# UIAPduino_Pro_Micro_CH32V006_V1dot1.net
KiCad netlist of a schematic drawn in EAGLE
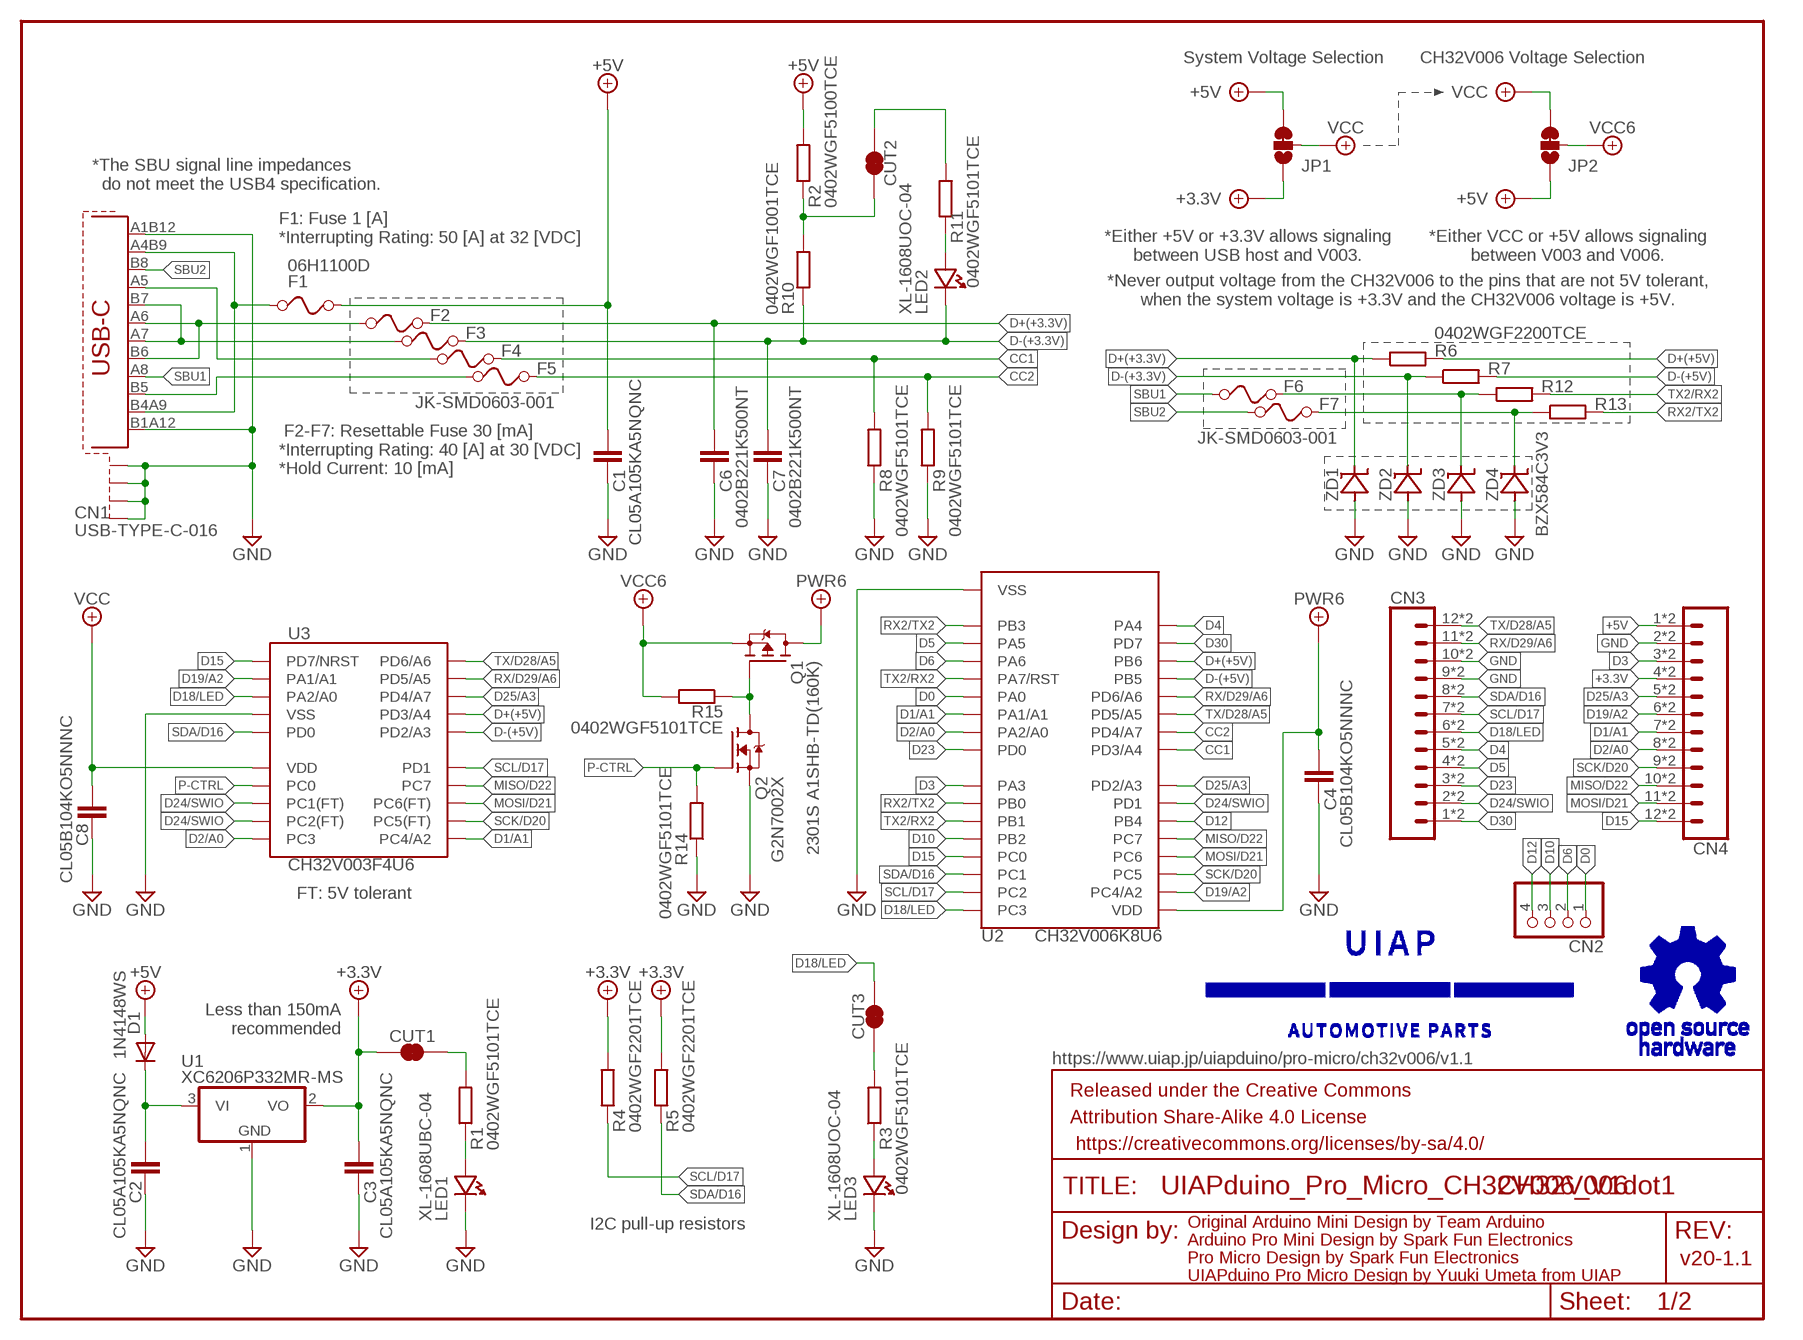
[diagram p0: schematic, sheet 1]
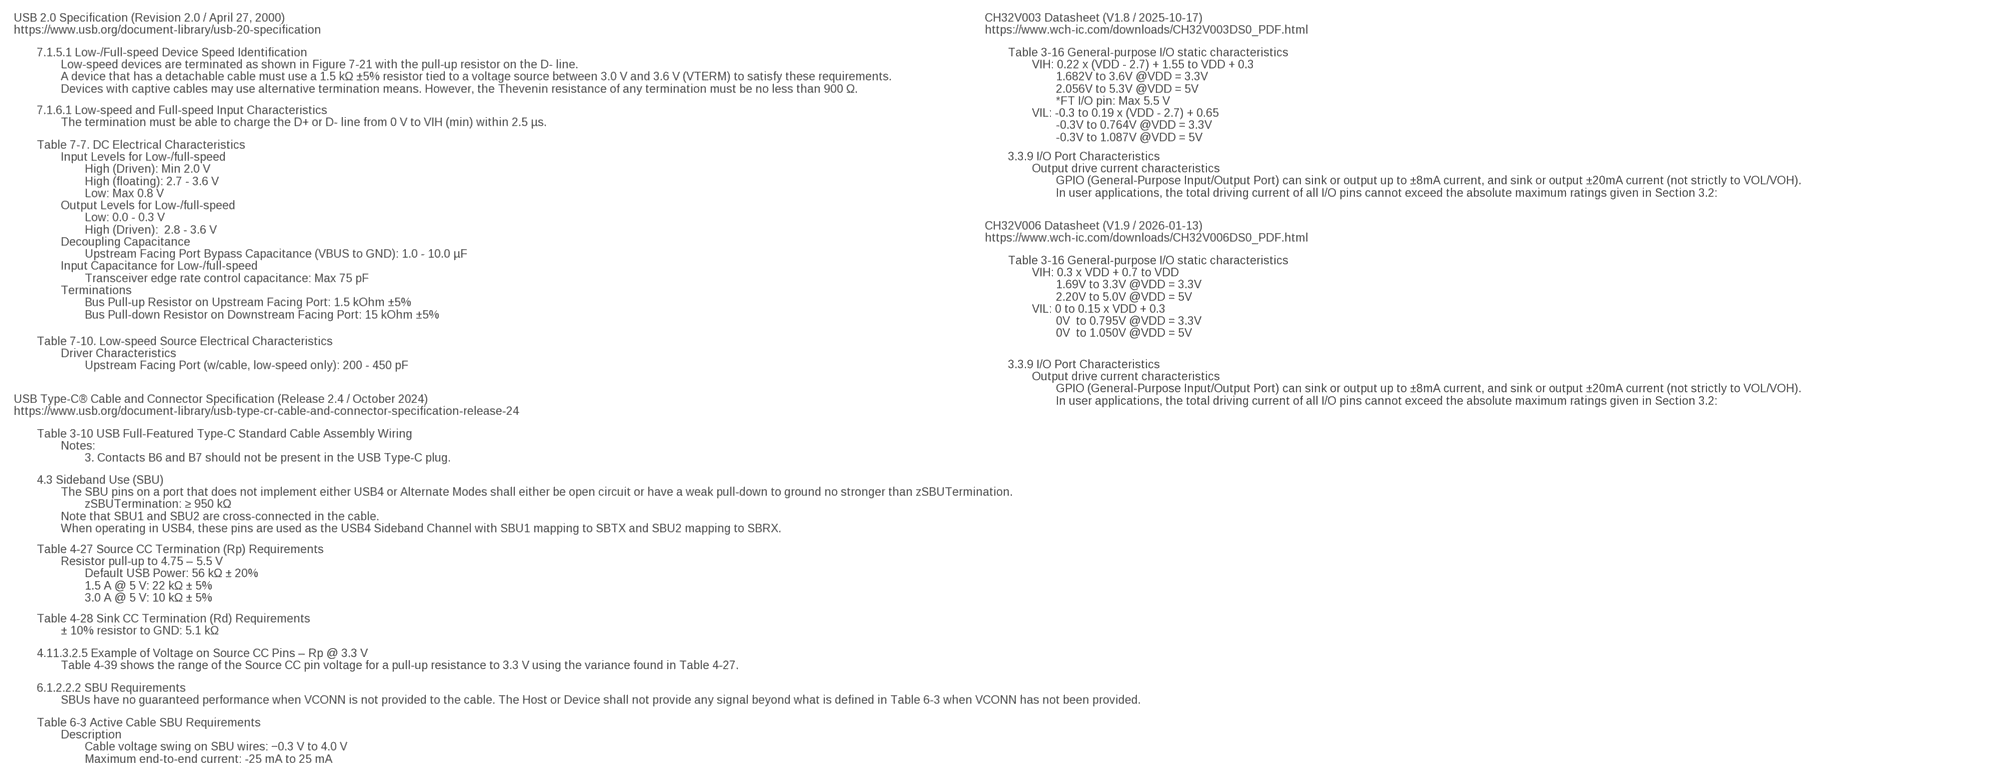
[diagram p1: schematic, sheet 2]

(export (version "E")
  (design (tool "Eeschema 10.0.6"))
  (components
    (comp (ref "C1")
      (value "CL05A105KA5NQNC")
      (footprint "eagle-import:1005")
      (libsource (lib "eagle-import") (part "C1005"))
    )
    (comp (ref "C2")
      (value "CL05A105KA5NQNC")
      (footprint "eagle-import:1005")
      (libsource (lib "eagle-import") (part "C1005"))
    )
    (comp (ref "C3")
      (value "CL05A105KA5NQNC")
      (footprint "eagle-import:1005")
      (libsource (lib "eagle-import") (part "C1005"))
    )
    (comp (ref "C4")
      (value "CL05B104KO5NNNC")
      (footprint "eagle-import:1005")
      (libsource (lib "eagle-import") (part "C1005"))
    )
    (comp (ref "C6")
      (value "0402B221K500NT")
      (footprint "eagle-import:1005")
      (libsource (lib "eagle-import") (part "C1005"))
    )
    (comp (ref "C7")
      (value "0402B221K500NT")
      (footprint "eagle-import:1005")
      (libsource (lib "eagle-import") (part "C1005"))
    )
    (comp (ref "C8")
      (value "CL05B104KO5NNNC")
      (footprint "eagle-import:1005")
      (libsource (lib "eagle-import") (part "C1005"))
    )
    (comp (ref "CN1")
      (value "USB-TYPE-C-016")
      (footprint "eagle-import:USB-TYPE-C-016")
      (libsource (lib "eagle-import") (part "USB-TYPE-C-016"))
    )
    (comp (ref "CN2")
      (value "PH-2X2")
      (footprint "eagle-import:2X02")
      (libsource (lib "eagle-import") (part "PH-2X2"))
    )
    (comp (ref "CN3")
      (value "CONN_12CASTLE_0.9MM")
      (footprint "eagle-import:1X12_CASTELLATED_0.9MM")
      (libsource (lib "eagle-import") (part "CONN_12CASTLE_0.9MM"))
    )
    (comp (ref "CN4")
      (value "CONN_12CASTLE_0.9MM")
      (footprint "eagle-import:1X12_CASTELLATED_0.9MM")
      (libsource (lib "eagle-import") (part "CONN_12CASTLE_0.9MM"))
    )
    (comp (ref "CUT1")
      (value "SMT-JP-2-NC")
      (footprint "eagle-import:SMT-JUMPER_2_NC_SILK_ROUND")
      (libsource (lib "eagle-import") (part "SMT-JP-2-NC"))
    )
    (comp (ref "CUT2")
      (value "SMT-JP-2-NC")
      (footprint "eagle-import:SMT-JUMPER_2_NC_SILK_ROUND")
      (libsource (lib "eagle-import") (part "SMT-JP-2-NC"))
    )
    (comp (ref "CUT3")
      (value "SMT-JP-2-NC")
      (footprint "eagle-import:SMT-JUMPER_2_NC_SILK_ROUND")
      (libsource (lib "eagle-import") (part "SMT-JP-2-NC"))
    )
    (comp (ref "D1")
      (value "1N4148WS")
      (footprint "eagle-import:SOD-523")
      (libsource (lib "eagle-import") (part "1N4148WT"))
    )
    (comp (ref "F1")
      (value "06H1100D")
      (footprint "eagle-import:1608")
      (libsource (lib "eagle-import") (part "06H1100D"))
    )
    (comp (ref "F2")
      (value "JK-SMD0603-001")
      (footprint "eagle-import:1608")
      (fields
        (field (name "JLCPCB-PART-#") "C2687114")
        (field (name "URL") "https://jlcpcb.com/partdetail/2790518-Jinrui_JK_SMD0603001/C2687114")
      )
      (libsource (lib "eagle-import") (part "06H1100D"))
    )
    (comp (ref "F3")
      (value "JK-SMD0603-001")
      (footprint "eagle-import:1608")
      (fields
        (field (name "JLCPCB-PART-#") "C2687114")
        (field (name "URL") "https://jlcpcb.com/partdetail/2790518-Jinrui_JK_SMD0603001/C2687114")
      )
      (libsource (lib "eagle-import") (part "06H1100D"))
    )
    (comp (ref "F4")
      (value "JK-SMD0603-001")
      (footprint "eagle-import:1608")
      (fields
        (field (name "JLCPCB-PART-#") "C2687114")
        (field (name "URL") "https://jlcpcb.com/partdetail/2790518-Jinrui_JK_SMD0603001/C2687114")
      )
      (libsource (lib "eagle-import") (part "06H1100D"))
    )
    (comp (ref "F5")
      (value "JK-SMD0603-001")
      (footprint "eagle-import:1608")
      (fields
        (field (name "JLCPCB-PART-#") "C2687114")
        (field (name "URL") "https://jlcpcb.com/partdetail/2790518-Jinrui_JK_SMD0603001/C2687114")
      )
      (libsource (lib "eagle-import") (part "06H1100D"))
    )
    (comp (ref "F6")
      (value "JK-SMD0603-001")
      (footprint "eagle-import:1608")
      (fields
        (field (name "JLCPCB-PART-#") "C2687114")
        (field (name "URL") "https://jlcpcb.com/partdetail/2790518-Jinrui_JK_SMD0603001/C2687114")
      )
      (libsource (lib "eagle-import") (part "06H1100D"))
    )
    (comp (ref "F7")
      (value "JK-SMD0603-001")
      (footprint "eagle-import:1608")
      (fields
        (field (name "JLCPCB-PART-#") "C2687114")
        (field (name "URL") "https://jlcpcb.com/partdetail/2790518-Jinrui_JK_SMD0603001/C2687114")
      )
      (libsource (lib "eagle-import") (part "06H1100D"))
    )
    (comp (ref "FRAME1")
      (value "FRAME-LETTER")
      (footprint "eagle-import:CREATIVE_COMMONS")
      (libsource (lib "eagle-import") (part "FRAME-LETTER"))
    )
    (comp (ref "JP1")
      (value "SMT-JP-3-NO-NC")
      (footprint "eagle-import:SMT-JUMPER_3_1-NC_TRACE_SILK")
      (libsource (lib "eagle-import") (part "SMT-JP-3-NO-NC"))
    )
    (comp (ref "JP2")
      (value "SMT-JP-3-NO-NC")
      (footprint "eagle-import:SMT-JUMPER_3_1-NC_TRACE_SILK")
      (libsource (lib "eagle-import") (part "SMT-JP-3-NO-NC"))
    )
    (comp (ref "LED1")
      (value "XL-1608UBC-04")
      (footprint "eagle-import:1608-LED")
      (libsource (lib "eagle-import") (part "XL-1608UBC-04"))
    )
    (comp (ref "LED2")
      (value "XL-1608UOC-04")
      (footprint "eagle-import:1608-LED")
      (libsource (lib "eagle-import") (part "XL-1608UOC-04"))
    )
    (comp (ref "LED3")
      (value "XL-1608UOC-04")
      (footprint "eagle-import:1608-LED")
      (libsource (lib "eagle-import") (part "XL-1608UOC-04"))
    )
    (comp (ref "Q1")
      (value "2301S A1SHB-TD(160K)")
      (footprint "eagle-import:SOT-23F_TOS-L")
      (libsource (lib "eagle-import") (part "2301S_A1SHB-TD(160K)"))
    )
    (comp (ref "Q2")
      (value "G2N7002X")
      (footprint "eagle-import:SOT-523")
      (libsource (lib "eagle-import") (part "G2N7002X"))
    )
    (comp (ref "R1")
      (value "0402WGF5101TCE")
      (footprint "eagle-import:1005")
      (libsource (lib "eagle-import") (part "R1005"))
    )
    (comp (ref "R2")
      (value "0402WGF5100TCE")
      (footprint "eagle-import:1005")
      (libsource (lib "eagle-import") (part "R1005"))
    )
    (comp (ref "R3")
      (value "0402WGF5101TCE")
      (footprint "eagle-import:1005")
      (libsource (lib "eagle-import") (part "R1005"))
    )
    (comp (ref "R4")
      (value "0402WGF2201TCE")
      (footprint "eagle-import:1005")
      (libsource (lib "eagle-import") (part "R1005"))
    )
    (comp (ref "R5")
      (value "0402WGF2201TCE")
      (footprint "eagle-import:1005")
      (libsource (lib "eagle-import") (part "R1005"))
    )
    (comp (ref "R6")
      (value "0402WGF2200TCE")
      (footprint "eagle-import:1005")
      (libsource (lib "eagle-import") (part "R1005"))
    )
    (comp (ref "R7")
      (value "0402WGF2200TCE")
      (footprint "eagle-import:1005")
      (libsource (lib "eagle-import") (part "R1005"))
    )
    (comp (ref "R8")
      (value "0402WGF5101TCE")
      (footprint "eagle-import:1005")
      (libsource (lib "eagle-import") (part "R1005"))
    )
    (comp (ref "R9")
      (value "0402WGF5101TCE")
      (footprint "eagle-import:1005")
      (libsource (lib "eagle-import") (part "R1005"))
    )
    (comp (ref "R10")
      (value "0402WGF1001TCE")
      (footprint "eagle-import:1005")
      (libsource (lib "eagle-import") (part "R1005"))
    )
    (comp (ref "R11")
      (value "0402WGF5101TCE")
      (footprint "eagle-import:1005")
      (libsource (lib "eagle-import") (part "R1005"))
    )
    (comp (ref "R12")
      (value "0402WGF2200TCE")
      (footprint "eagle-import:1005")
      (libsource (lib "eagle-import") (part "R1005"))
    )
    (comp (ref "R13")
      (value "0402WGF2200TCE")
      (footprint "eagle-import:1005")
      (libsource (lib "eagle-import") (part "R1005"))
    )
    (comp (ref "R14")
      (value "0402WGF5101TCE")
      (footprint "eagle-import:1005")
      (libsource (lib "eagle-import") (part "R1005"))
    )
    (comp (ref "R15")
      (value "0402WGF5101TCE")
      (footprint "eagle-import:1005")
      (libsource (lib "eagle-import") (part "R1005"))
    )
    (comp (ref "U1")
      (value "XC6206P332MR-MS")
      (footprint "eagle-import:SOT-23F_TOS-L")
      (libsource (lib "eagle-import") (part "XC6206P332MR-MS"))
    )
    (comp (ref "U2")
      (value "CH32V006K8U6")
      (footprint "eagle-import:QFN32-400X400X100")
      (libsource (lib "eagle-import") (part "CH32V006K8U6"))
    )
    (comp (ref "U3")
      (value "CH32V003F4U6")
      (footprint "eagle-import:QFN20-300X300X100-L")
      (libsource (lib "eagle-import") (part "CH32V003F4U6-L"))
    )
    (comp (ref "ZD1")
      (value "BZX584C3V3")
      (footprint "eagle-import:SOD-523")
      (libsource (lib "eagle-import") (part "BZX584C3V3"))
    )
    (comp (ref "ZD2")
      (value "BZX584C3V3")
      (footprint "eagle-import:SOD-523")
      (libsource (lib "eagle-import") (part "BZX584C3V3"))
    )
    (comp (ref "ZD3")
      (value "BZX584C3V3")
      (footprint "eagle-import:SOD-523")
      (libsource (lib "eagle-import") (part "BZX584C3V3"))
    )
    (comp (ref "ZD4")
      (value "BZX584C3V3")
      (footprint "eagle-import:SOD-523")
      (libsource (lib "eagle-import") (part "BZX584C3V3"))
    )
  )
  (nets
    (net (code "1") (name "+3.3V") (class "Default")
      (node (ref "C3") (pin "1") (pinfunction "1_1") (pintype "passive"))
      (node (ref "CN4") (pin "4") (pinfunction "4_4") (pintype "passive"))
      (node (ref "CN4") (pin "4B") (pinfunction "4_4B") (pintype "passive"))
      (node (ref "CUT1") (pin "2") (pinfunction "2_2") (pintype "passive"))
      (node (ref "JP1") (pin "1") (pinfunction "1_1") (pintype "passive"))
      (node (ref "R4") (pin "2") (pinfunction "2_2") (pintype "passive"))
      (node (ref "R5") (pin "2") (pinfunction "2_2") (pintype "passive"))
      (node (ref "U1") (pin "2") (pinfunction "VO_2") (pintype "passive"))
    )
    (net (code "2") (name "+5V") (class "Default")
      (node (ref "C1") (pin "1") (pinfunction "1_1") (pintype "passive"))
      (node (ref "CN4") (pin "1") (pinfunction "1_1") (pintype "passive"))
      (node (ref "CN4") (pin "1B") (pinfunction "1_1B") (pintype "passive"))
      (node (ref "D1") (pin "2") (pinfunction "A_2") (pintype "passive"))
      (node (ref "F1") (pin "2") (pinfunction "2_2") (pintype "passive"))
      (node (ref "JP1") (pin "3") (pinfunction "3_3") (pintype "passive"))
      (node (ref "JP2") (pin "1") (pinfunction "1_1") (pintype "passive"))
      (node (ref "R2") (pin "2") (pinfunction "2_2") (pintype "passive"))
    )
    (net (code "3") (name "CC1") (class "Default")
      (node (ref "F4") (pin "2") (pinfunction "2_2") (pintype "passive"))
      (node (ref "R8") (pin "2") (pinfunction "2_2") (pintype "passive"))
      (node (ref "U2") (pin "25") (pinfunction "PD3/A4_25") (pintype "bidirectional"))
    )
    (net (code "4") (name "CC2") (class "Default")
      (node (ref "F5") (pin "2") (pinfunction "2_2") (pintype "passive"))
      (node (ref "R9") (pin "2") (pinfunction "2_2") (pintype "passive"))
      (node (ref "U2") (pin "26") (pinfunction "PD4/A7_26") (pintype "bidirectional"))
    )
    (net (code "5") (name "D+(+3.3V)") (class "Default")
      (node (ref "C6") (pin "1") (pinfunction "1_1") (pintype "passive"))
      (node (ref "F2") (pin "2") (pinfunction "2_2") (pintype "passive"))
      (node (ref "R6") (pin "1") (pinfunction "1_1") (pintype "passive"))
      (node (ref "ZD1") (pin "1") (pinfunction "C_1") (pintype "passive"))
    )
    (net (code "6") (name "D+(+5V)") (class "Default")
      (node (ref "R6") (pin "2") (pinfunction "2_2") (pintype "passive"))
      (node (ref "U2") (pin "30") (pinfunction "PB6_30") (pintype "bidirectional"))
      (node (ref "U3") (pin "17") (pinfunction "PD3/A4_17") (pintype "bidirectional"))
    )
    (net (code "7") (name "D-(+3.3V)") (class "Default")
      (node (ref "C7") (pin "1") (pinfunction "1_1") (pintype "passive"))
      (node (ref "F3") (pin "2") (pinfunction "2_2") (pintype "passive"))
      (node (ref "LED2") (pin "2") (pinfunction "C_2") (pintype "passive"))
      (node (ref "R10") (pin "1") (pinfunction "1_1") (pintype "passive"))
      (node (ref "R7") (pin "1") (pinfunction "1_1") (pintype "passive"))
      (node (ref "ZD2") (pin "1") (pinfunction "C_1") (pintype "passive"))
    )
    (net (code "8") (name "D-(+5V)") (class "Default")
      (node (ref "R7") (pin "2") (pinfunction "2_2") (pintype "passive"))
      (node (ref "U2") (pin "29") (pinfunction "PB5_29") (pintype "bidirectional"))
      (node (ref "U3") (pin "16") (pinfunction "PD2/A3_16") (pintype "bidirectional"))
    )
    (net (code "9") (name "D0") (class "Default")
      (node (ref "CN2") (pin "1") (pinfunction "1_1") (pintype "passive"))
      (node (ref "U2") (pin "5") (pinfunction "PA0_5") (pintype "bidirectional"))
    )
    (net (code "10") (name "D1{slash}A1") (class "Default")
      (node (ref "CN4") (pin "7") (pinfunction "7_7") (pintype "passive"))
      (node (ref "CN4") (pin "7B") (pinfunction "7_7B") (pintype "passive"))
      (node (ref "U2") (pin "6") (pinfunction "PA1/A1_6") (pintype "bidirectional"))
      (node (ref "U3") (pin "11") (pinfunction "PC4/A2_11") (pintype "bidirectional"))
    )
    (net (code "11") (name "D2{slash}A0") (class "Default")
      (node (ref "CN4") (pin "8") (pinfunction "8_8") (pintype "passive"))
      (node (ref "CN4") (pin "8B") (pinfunction "8_8B") (pintype "passive"))
      (node (ref "U2") (pin "7") (pinfunction "PA2/A0_7") (pintype "bidirectional"))
      (node (ref "U3") (pin "10") (pinfunction "PC3_10") (pintype "bidirectional"))
    )
    (net (code "12") (name "D3") (class "Default")
      (node (ref "CN4") (pin "3") (pinfunction "3_3") (pintype "passive"))
      (node (ref "CN4") (pin "3B") (pinfunction "3_3B") (pintype "passive"))
      (node (ref "U2") (pin "9") (pinfunction "PA3_9") (pintype "bidirectional"))
    )
    (net (code "13") (name "D4") (class "Default")
      (node (ref "CN3") (pin "5") (pinfunction "5_5") (pintype "passive"))
      (node (ref "CN3") (pin "5B") (pinfunction "5_5B") (pintype "passive"))
      (node (ref "U2") (pin "32") (pinfunction "PA4_32") (pintype "bidirectional"))
    )
    (net (code "14") (name "D5") (class "Default")
      (node (ref "CN3") (pin "4") (pinfunction "4_4") (pintype "passive"))
      (node (ref "CN3") (pin "4B") (pinfunction "4_4B") (pintype "passive"))
      (node (ref "U2") (pin "2") (pinfunction "PA5_2") (pintype "bidirectional"))
    )
    (net (code "15") (name "D6") (class "Default")
      (node (ref "CN2") (pin "2") (pinfunction "2_2") (pintype "passive"))
      (node (ref "U2") (pin "3") (pinfunction "PA6_3") (pintype "bidirectional"))
    )
    (net (code "16") (name "D10") (class "Default")
      (node (ref "CN2") (pin "3") (pinfunction "3_3") (pintype "passive"))
      (node (ref "U2") (pin "12") (pinfunction "PB2_12") (pintype "bidirectional"))
    )
    (net (code "17") (name "D12") (class "Default")
      (node (ref "CN2") (pin "4") (pinfunction "4_4") (pintype "passive"))
      (node (ref "U2") (pin "22") (pinfunction "PB4_22") (pintype "bidirectional"))
    )
    (net (code "18") (name "D15") (class "Default")
      (node (ref "CN4") (pin "12") (pinfunction "12_12") (pintype "passive"))
      (node (ref "CN4") (pin "12B") (pinfunction "12_12B") (pintype "passive"))
      (node (ref "U2") (pin "13") (pinfunction "PC0_13") (pintype "bidirectional"))
      (node (ref "U3") (pin "1") (pinfunction "PD7/NRST_1") (pintype "bidirectional"))
    )
    (net (code "19") (name "D18{slash}LED") (class "Default")
      (node (ref "CN3") (pin "6") (pinfunction "6_6") (pintype "passive"))
      (node (ref "CN3") (pin "6B") (pinfunction "6_6B") (pintype "passive"))
      (node (ref "CUT3") (pin "1") (pinfunction "1_1") (pintype "passive"))
      (node (ref "U2") (pin "16") (pinfunction "PC3_16") (pintype "bidirectional"))
      (node (ref "U3") (pin "3") (pinfunction "PA2/A0_3") (pintype "bidirectional"))
    )
    (net (code "20") (name "D19{slash}A2") (class "Default")
      (node (ref "CN4") (pin "6") (pinfunction "6_6") (pintype "passive"))
      (node (ref "CN4") (pin "6B") (pinfunction "6_6B") (pintype "passive"))
      (node (ref "U2") (pin "18") (pinfunction "PC4/A2_18") (pintype "bidirectional"))
      (node (ref "U3") (pin "2") (pinfunction "PA1/A1_2") (pintype "bidirectional"))
    )
    (net (code "21") (name "D23") (class "Default")
      (node (ref "CN3") (pin "3") (pinfunction "3_3") (pintype "passive"))
      (node (ref "CN3") (pin "3B") (pinfunction "3_3B") (pintype "passive"))
      (node (ref "U2") (pin "8") (pinfunction "PD0_8") (pintype "bidirectional"))
    )
    (net (code "22") (name "D24{slash}SWIO") (class "Default")
      (node (ref "CN3") (pin "2") (pinfunction "2_2") (pintype "passive"))
      (node (ref "CN3") (pin "2B") (pinfunction "2_2B") (pintype "passive"))
      (node (ref "U2") (pin "23") (pinfunction "PD1_23") (pintype "bidirectional"))
      (node (ref "U3") (pin "8") (pinfunction "PC1(FT)_8") (pintype "bidirectional"))
      (node (ref "U3") (pin "9") (pinfunction "PC2(FT)_9") (pintype "bidirectional"))
    )
    (net (code "23") (name "D25{slash}A3") (class "Default")
      (node (ref "CN4") (pin "5") (pinfunction "5_5") (pintype "passive"))
      (node (ref "CN4") (pin "5B") (pinfunction "5_5B") (pintype "passive"))
      (node (ref "U2") (pin "24") (pinfunction "PD2/A3_24") (pintype "bidirectional"))
      (node (ref "U3") (pin "18") (pinfunction "PD4/A7_18") (pintype "bidirectional"))
    )
    (net (code "24") (name "D30") (class "Default")
      (node (ref "CN3") (pin "1") (pinfunction "1_1") (pintype "passive"))
      (node (ref "CN3") (pin "1B") (pinfunction "1_1B") (pintype "passive"))
      (node (ref "U2") (pin "31") (pinfunction "PD7_31") (pintype "bidirectional"))
    )
    (net (code "25") (name "GND") (class "Default")
      (node (ref "C1") (pin "2") (pinfunction "2_2") (pintype "passive"))
      (node (ref "C2") (pin "2") (pinfunction "2_2") (pintype "passive"))
      (node (ref "C3") (pin "2") (pinfunction "2_2") (pintype "passive"))
      (node (ref "C4") (pin "2") (pinfunction "2_2") (pintype "passive"))
      (node (ref "C6") (pin "2") (pinfunction "2_2") (pintype "passive"))
      (node (ref "C7") (pin "2") (pinfunction "2_2") (pintype "passive"))
      (node (ref "C8") (pin "2") (pinfunction "2_2") (pintype "passive"))
      (node (ref "CN1") (pin "A1B12") (pinfunction "GND_A1B12") (pintype "power_in"))
      (node (ref "CN1") (pin "B1A12") (pinfunction "GND_B1A12") (pintype "power_in"))
      (node (ref "CN1") (pin "S1") (pinfunction "S1_S1") (pintype "passive"))
      (node (ref "CN1") (pin "S1B") (pinfunction "S1_S1B") (pintype "passive"))
      (node (ref "CN1") (pin "S2") (pinfunction "S2_S2") (pintype "passive"))
      (node (ref "CN1") (pin "S2B") (pinfunction "S2_S2B") (pintype "passive"))
      (node (ref "CN1") (pin "S3") (pinfunction "S3_S3") (pintype "passive"))
      (node (ref "CN1") (pin "S3B") (pinfunction "S3_S3B") (pintype "passive"))
      (node (ref "CN1") (pin "S4") (pinfunction "S4_S4") (pintype "passive"))
      (node (ref "CN1") (pin "S4B") (pinfunction "S4_S4B") (pintype "passive"))
      (node (ref "CN3") (pin "10") (pinfunction "10_10") (pintype "passive"))
      (node (ref "CN3") (pin "10B") (pinfunction "10_10B") (pintype "passive"))
      (node (ref "CN3") (pin "9") (pinfunction "9_9") (pintype "passive"))
      (node (ref "CN3") (pin "9B") (pinfunction "9_9B") (pintype "passive"))
      (node (ref "CN4") (pin "2") (pinfunction "2_2") (pintype "passive"))
      (node (ref "CN4") (pin "2B") (pinfunction "2_2B") (pintype "passive"))
      (node (ref "LED1") (pin "2") (pinfunction "C_2") (pintype "passive"))
      (node (ref "LED3") (pin "2") (pinfunction "C_2") (pintype "passive"))
      (node (ref "Q2") (pin "2") (pinfunction "S_2") (pintype "passive"))
      (node (ref "R14") (pin "1") (pinfunction "1_1") (pintype "passive"))
      (node (ref "R8") (pin "1") (pinfunction "1_1") (pintype "passive"))
      (node (ref "R9") (pin "1") (pinfunction "1_1") (pintype "passive"))
      (node (ref "U1") (pin "1") (pinfunction "GND_1") (pintype "passive"))
      (node (ref "U2") (pin "0") (pinfunction "VSS_0") (pintype "power_in"))
      (node (ref "U2") (pin "P-VIA$1") (pinfunction "VSS_P-VIA$1") (pintype "power_in"))
      (node (ref "U2") (pin "P-VIA$5") (pinfunction "VSS_P-VIA$5") (pintype "power_in"))
      (node (ref "U2") (pin "P-VIA$6") (pinfunction "VSS_P-VIA$6") (pintype "power_in"))
      (node (ref "U2") (pin "P-VIA$8") (pinfunction "VSS_P-VIA$8") (pintype "power_in"))
      (node (ref "U2") (pin "P-VIA$9") (pinfunction "VSS_P-VIA$9") (pintype "power_in"))
      (node (ref "U3") (pin "21") (pinfunction "VSS_21") (pintype "power_in"))
      (node (ref "U3") (pin "4") (pinfunction "VSS_4") (pintype "power_in"))
      (node (ref "U3") (pin "P-VIA$1") (pinfunction "VSS_P-VIA$1") (pintype "power_in"))
      (node (ref "ZD1") (pin "2") (pinfunction "A_2") (pintype "passive"))
      (node (ref "ZD2") (pin "2") (pinfunction "A_2") (pintype "passive"))
      (node (ref "ZD3") (pin "2") (pinfunction "A_2") (pintype "passive"))
      (node (ref "ZD4") (pin "2") (pinfunction "A_2") (pintype "passive"))
    )
    (net (code "26") (name "MISO{slash}D22") (class "Default")
      (node (ref "CN4") (pin "10") (pinfunction "10_10") (pintype "passive"))
      (node (ref "CN4") (pin "10B") (pinfunction "10_10B") (pintype "passive"))
      (node (ref "U2") (pin "21") (pinfunction "PC7_21") (pintype "bidirectional"))
      (node (ref "U3") (pin "14") (pinfunction "PC7_14") (pintype "bidirectional"))
    )
    (net (code "27") (name "MOSI{slash}D21") (class "Default")
      (node (ref "CN4") (pin "11") (pinfunction "11_11") (pintype "passive"))
      (node (ref "CN4") (pin "11B") (pinfunction "11_11B") (pintype "passive"))
      (node (ref "U2") (pin "20") (pinfunction "PC6_20") (pintype "bidirectional"))
      (node (ref "U3") (pin "13") (pinfunction "PC6(FT)_13") (pintype "bidirectional"))
    )
    (net (code "28") (name "Net-(CN1-CC1)") (class "Default")
      (node (ref "CN1") (pin "A5") (pinfunction "CC1_A5") (pintype "passive"))
      (node (ref "F4") (pin "1") (pinfunction "1_1") (pintype "passive"))
    )
    (net (code "29") (name "Net-(CN1-CC2)") (class "Default")
      (node (ref "CN1") (pin "B5") (pinfunction "CC2_B5") (pintype "passive"))
      (node (ref "F5") (pin "1") (pinfunction "1_1") (pintype "passive"))
    )
    (net (code "30") (name "Net-(CN1-DN1)") (class "Default")
      (node (ref "CN1") (pin "A7") (pinfunction "DN1_A7") (pintype "passive"))
      (node (ref "CN1") (pin "B7") (pinfunction "DN2_B7") (pintype "passive"))
      (node (ref "F3") (pin "1") (pinfunction "1_1") (pintype "passive"))
    )
    (net (code "31") (name "Net-(CN1-DP1)") (class "Default")
      (node (ref "CN1") (pin "A6") (pinfunction "DP1_A6") (pintype "passive"))
      (node (ref "CN1") (pin "B6") (pinfunction "DP2_B6") (pintype "passive"))
      (node (ref "F2") (pin "1") (pinfunction "1_1") (pintype "passive"))
    )
    (net (code "32") (name "Net-(CN1-VBUS-PadA4B9)") (class "Default")
      (node (ref "CN1") (pin "A4B9") (pinfunction "VBUS_A4B9") (pintype "power_in"))
      (node (ref "CN1") (pin "B4A9") (pinfunction "VBUS_B4A9") (pintype "power_in"))
      (node (ref "F1") (pin "1") (pinfunction "1_1") (pintype "passive"))
    )
    (net (code "33") (name "Net-(CUT1-Pad1)") (class "Default")
      (node (ref "CUT1") (pin "1") (pinfunction "1_1") (pintype "passive"))
      (node (ref "R1") (pin "2") (pinfunction "2_2") (pintype "passive"))
    )
    (net (code "34") (name "Net-(CUT2-Pad1)") (class "Default")
      (node (ref "CUT2") (pin "1") (pinfunction "1_1") (pintype "passive"))
      (node (ref "R11") (pin "2") (pinfunction "2_2") (pintype "passive"))
    )
    (net (code "35") (name "Net-(CUT2-Pad2)") (class "Default")
      (node (ref "CUT2") (pin "2") (pinfunction "2_2") (pintype "passive"))
      (node (ref "R10") (pin "2") (pinfunction "2_2") (pintype "passive"))
      (node (ref "R2") (pin "1") (pinfunction "1_1") (pintype "passive"))
    )
    (net (code "36") (name "Net-(CUT3-Pad2)") (class "Default")
      (node (ref "CUT3") (pin "2") (pinfunction "2_2") (pintype "passive"))
      (node (ref "R3") (pin "2") (pinfunction "2_2") (pintype "passive"))
    )
    (net (code "37") (name "Net-(D1-C)") (class "Default")
      (node (ref "C2") (pin "1") (pinfunction "1_1") (pintype "passive"))
      (node (ref "D1") (pin "1") (pinfunction "C_1") (pintype "passive"))
      (node (ref "U1") (pin "3") (pinfunction "VI_3") (pintype "input"))
    )
    (net (code "38") (name "Net-(LED1-A)") (class "Default")
      (node (ref "LED1") (pin "1") (pinfunction "A_1") (pintype "passive"))
      (node (ref "R1") (pin "1") (pinfunction "1_1") (pintype "passive"))
    )
    (net (code "39") (name "Net-(LED2-A)") (class "Default")
      (node (ref "LED2") (pin "1") (pinfunction "A_1") (pintype "passive"))
      (node (ref "R11") (pin "1") (pinfunction "1_1") (pintype "passive"))
    )
    (net (code "40") (name "Net-(LED3-A)") (class "Default")
      (node (ref "LED3") (pin "1") (pinfunction "A_1") (pintype "passive"))
      (node (ref "R3") (pin "1") (pinfunction "1_1") (pintype "passive"))
    )
    (net (code "41") (name "Net-(Q1-G)") (class "Default")
      (node (ref "Q1") (pin "1") (pinfunction "G_1") (pintype "passive"))
      (node (ref "Q2") (pin "3") (pinfunction "D_3") (pintype "passive"))
      (node (ref "R15") (pin "1") (pinfunction "1_1") (pintype "passive"))
    )
    (net (code "42") (name "Net-(ZD3-C)") (class "Default")
      (node (ref "F6") (pin "2") (pinfunction "2_2") (pintype "passive"))
      (node (ref "R12") (pin "1") (pinfunction "1_1") (pintype "passive"))
      (node (ref "ZD3") (pin "1") (pinfunction "C_1") (pintype "passive"))
    )
    (net (code "43") (name "Net-(ZD4-C)") (class "Default")
      (node (ref "F7") (pin "2") (pinfunction "2_2") (pintype "passive"))
      (node (ref "R13") (pin "1") (pinfunction "1_1") (pintype "passive"))
      (node (ref "ZD4") (pin "1") (pinfunction "C_1") (pintype "passive"))
    )
    (net (code "44") (name "P-CTRL") (class "Default")
      (node (ref "Q2") (pin "1") (pinfunction "G_1") (pintype "passive"))
      (node (ref "R14") (pin "2") (pinfunction "2_2") (pintype "passive"))
      (node (ref "U3") (pin "7") (pinfunction "PC0_7") (pintype "bidirectional"))
    )
    (net (code "45") (name "PWR6") (class "Default")
      (node (ref "C4") (pin "1") (pinfunction "1_1") (pintype "passive"))
      (node (ref "Q1") (pin "3") (pinfunction "D_3") (pintype "passive"))
      (node (ref "U2") (pin "17") (pinfunction "VDD_17") (pintype "power_in"))
    )
    (net (code "46") (name "RX2{slash}TX2") (class "Default")
      (node (ref "R13") (pin "2") (pinfunction "2_2") (pintype "passive"))
      (node (ref "U2") (pin "1") (pinfunction "PB3_1") (pintype "bidirectional"))
      (node (ref "U2") (pin "10") (pinfunction "PB0_10") (pintype "bidirectional"))
    )
    (net (code "47") (name "RX{slash}D29{slash}A6") (class "Default")
      (node (ref "CN3") (pin "11") (pinfunction "11_11") (pintype "passive"))
      (node (ref "CN3") (pin "11B") (pinfunction "11_11B") (pintype "passive"))
      (node (ref "U2") (pin "28") (pinfunction "PD6/A6_28") (pintype "bidirectional"))
      (node (ref "U3") (pin "19") (pinfunction "PD5/A5_19") (pintype "bidirectional"))
    )
    (net (code "48") (name "SBU1") (class "Default")
      (node (ref "CN1") (pin "A8") (pinfunction "SBU1_A8") (pintype "passive"))
      (node (ref "F6") (pin "1") (pinfunction "1_1") (pintype "passive"))
    )
    (net (code "49") (name "SBU2") (class "Default")
      (node (ref "CN1") (pin "B8") (pinfunction "SBU2_B8") (pintype "passive"))
      (node (ref "F7") (pin "1") (pinfunction "1_1") (pintype "passive"))
    )
    (net (code "50") (name "SCK{slash}D20") (class "Default")
      (node (ref "CN4") (pin "9") (pinfunction "9_9") (pintype "passive"))
      (node (ref "CN4") (pin "9B") (pinfunction "9_9B") (pintype "passive"))
      (node (ref "U2") (pin "19") (pinfunction "PC5_19") (pintype "bidirectional"))
      (node (ref "U3") (pin "12") (pinfunction "PC5(FT)_12") (pintype "bidirectional"))
    )
    (net (code "51") (name "SCL{slash}D17") (class "Default")
      (node (ref "CN3") (pin "7") (pinfunction "7_7") (pintype "passive"))
      (node (ref "CN3") (pin "7B") (pinfunction "7_7B") (pintype "passive"))
      (node (ref "R4") (pin "1") (pinfunction "1_1") (pintype "passive"))
      (node (ref "U2") (pin "15") (pinfunction "PC2_15") (pintype "bidirectional"))
      (node (ref "U3") (pin "15") (pinfunction "PD1_15") (pintype "bidirectional"))
    )
    (net (code "52") (name "SDA{slash}D16") (class "Default")
      (node (ref "CN3") (pin "8") (pinfunction "8_8") (pintype "passive"))
      (node (ref "CN3") (pin "8B") (pinfunction "8_8B") (pintype "passive"))
      (node (ref "R5") (pin "1") (pinfunction "1_1") (pintype "passive"))
      (node (ref "U2") (pin "14") (pinfunction "PC1_14") (pintype "bidirectional"))
      (node (ref "U3") (pin "5") (pinfunction "PD0_5") (pintype "bidirectional"))
    )
    (net (code "53") (name "TX2{slash}RX2") (class "Default")
      (node (ref "R12") (pin "2") (pinfunction "2_2") (pintype "passive"))
      (node (ref "U2") (pin "11") (pinfunction "PB1_11") (pintype "bidirectional"))
      (node (ref "U2") (pin "4") (pinfunction "PA7/RST_4") (pintype "bidirectional"))
    )
    (net (code "54") (name "TX{slash}D28{slash}A5") (class "Default")
      (node (ref "CN3") (pin "12") (pinfunction "12_12") (pintype "passive"))
      (node (ref "CN3") (pin "12B") (pinfunction "12_12B") (pintype "passive"))
      (node (ref "U2") (pin "27") (pinfunction "PD5/A5_27") (pintype "bidirectional"))
      (node (ref "U3") (pin "20") (pinfunction "PD6/A6_20") (pintype "bidirectional"))
    )
    (net (code "55") (name "VCC") (class "Default")
      (node (ref "C8") (pin "1") (pinfunction "1_1") (pintype "passive"))
      (node (ref "JP1") (pin "2") (pinfunction "2_2") (pintype "passive"))
      (node (ref "JP2") (pin "3") (pinfunction "3_3") (pintype "passive"))
      (node (ref "U3") (pin "6") (pinfunction "VDD_6") (pintype "power_in"))
    )
    (net (code "56") (name "VCC6") (class "Default")
      (node (ref "JP2") (pin "2") (pinfunction "2_2") (pintype "passive"))
      (node (ref "Q1") (pin "2") (pinfunction "S_2") (pintype "passive"))
      (node (ref "R15") (pin "2") (pinfunction "2_2") (pintype "passive"))
    )
  )
)
